# SmartSwitch2.net
KiCad netlist of a schematic drawn in EAGLE
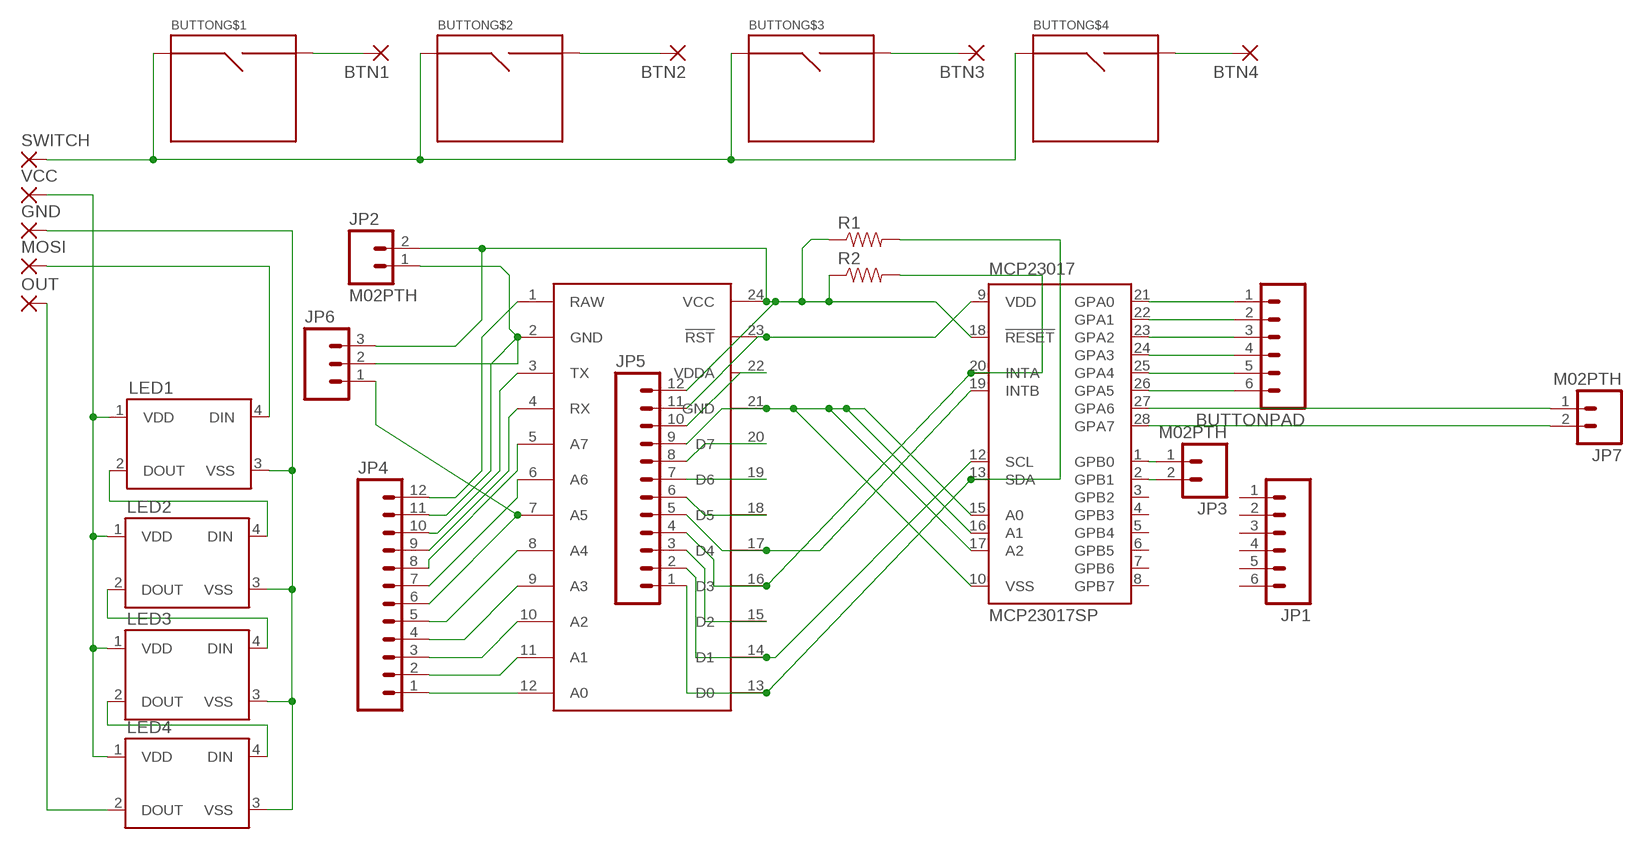
[diagram p0: schematic, sheet 1]

(export (version "E")
  (design (tool "Eeschema 10.0.6"))
  (components
    (comp (ref "BTN1")
      (value "2,15/1,0")
      (footprint "eagle-import:2,15_1,0")
      (libsource (lib "eagle-import") (part "2,15/1,0"))
    )
    (comp (ref "BTN2")
      (value "2,15/1,0")
      (footprint "eagle-import:2,15_1,0")
      (libsource (lib "eagle-import") (part "2,15/1,0"))
    )
    (comp (ref "BTN3")
      (value "2,15/1,0")
      (footprint "eagle-import:2,15_1,0")
      (libsource (lib "eagle-import") (part "2,15/1,0"))
    )
    (comp (ref "BTN4")
      (value "2,15/1,0")
      (footprint "eagle-import:2,15_1,0")
      (libsource (lib "eagle-import") (part "2,15/1,0"))
    )
    (comp (ref "BUTTON")
      (value "BUTTON")
      (footprint "eagle-import:BUTTON")
      (libsource (lib "eagle-import") (part "BUTTON"))
    )
    (comp (ref "BUTTONPAD")
      (value "M06SILK_FEMALE_PTH")
      (footprint "eagle-import:1X06")
      (libsource (lib "eagle-import") (part "M06SILK_FEMALE_PTH"))
    )
    (comp (ref "GND")
      (value "2,15/1,0")
      (footprint "eagle-import:2,15_1,0")
      (libsource (lib "eagle-import") (part "2,15/1,0"))
    )
    (comp (ref "JP1")
      (value "M06SILK_FEMALE_PTH")
      (footprint "eagle-import:1X06")
      (libsource (lib "eagle-import") (part "M06SILK_FEMALE_PTH"))
    )
    (comp (ref "JP2")
      (value "M02PTH")
      (footprint "eagle-import:1X02")
      (libsource (lib "eagle-import") (part "M02PTH"))
    )
    (comp (ref "JP3")
      (value "M02PTH")
      (footprint "eagle-import:1X02")
      (libsource (lib "eagle-import") (part "M02PTH"))
    )
    (comp (ref "JP4")
      (value "M12PTH")
      (footprint "eagle-import:1X12-SMALL-PADS")
      (libsource (lib "eagle-import") (part "M12PTH"))
    )
    (comp (ref "JP5")
      (value "M12PTH")
      (footprint "eagle-import:1X12-SMALL-PADS")
      (libsource (lib "eagle-import") (part "M12PTH"))
    )
    (comp (ref "JP6")
      (value "M03PTH")
      (footprint "eagle-import:1X03")
      (libsource (lib "eagle-import") (part "M03PTH"))
    )
    (comp (ref "JP7")
      (value "M02PTH")
      (footprint "eagle-import:1X02")
      (libsource (lib "eagle-import") (part "M02PTH"))
    )
    (comp (ref "LED1")
      (value "WS2812B")
      (footprint "eagle-import:WS2812B")
      (libsource (lib "eagle-import") (part "WS2812B"))
    )
    (comp (ref "LED2")
      (value "WS2812B")
      (footprint "eagle-import:WS2812B")
      (libsource (lib "eagle-import") (part "WS2812B"))
    )
    (comp (ref "LED3")
      (value "WS2812B")
      (footprint "eagle-import:WS2812B")
      (libsource (lib "eagle-import") (part "WS2812B"))
    )
    (comp (ref "LED4")
      (value "WS2812B")
      (footprint "eagle-import:WS2812B")
      (libsource (lib "eagle-import") (part "WS2812B"))
    )
    (comp (ref "MCP23017")
      (value "MCP23017SP")
      (footprint "eagle-import:DIL28-3")
      (libsource (lib "eagle-import") (part "MCP23017SP"))
    )
    (comp (ref "MOSI")
      (value "2,15/1,0")
      (footprint "eagle-import:2,15_1,0")
      (libsource (lib "eagle-import") (part "2,15/1,0"))
    )
    (comp (ref "OUT")
      (value "2,15/1,0")
      (footprint "eagle-import:2,15_1,0")
      (libsource (lib "eagle-import") (part "2,15/1,0"))
    )
    (comp (ref "R1")
      (value "RESISTORPTH-1/2W")
      (footprint "eagle-import:AXIAL-0.5")
      (libsource (lib "eagle-import") (part "RESISTORPTH-1/2W"))
    )
    (comp (ref "R2")
      (value "RESISTORPTH-1/2W")
      (footprint "eagle-import:AXIAL-0.5")
      (libsource (lib "eagle-import") (part "RESISTORPTH-1/2W"))
    )
    (comp (ref "SPARK")
      (value "SPARK_CORECORE")
      (footprint "eagle-import:SPARK_CORE")
      (libsource (lib "eagle-import") (part "SPARK_CORECORE"))
    )
    (comp (ref "SWITCH")
      (value "2,15/1,0")
      (footprint "eagle-import:2,15_1,0")
      (libsource (lib "eagle-import") (part "2,15/1,0"))
    )
    (comp (ref "VCC")
      (value "2,15/1,0")
      (footprint "eagle-import:2,15_1,0")
      (libsource (lib "eagle-import") (part "2,15/1,0"))
    )
  )
  (nets
    (net (code "1") (name "Net-(BTN1-P)") (class "Default")
      (node (ref "BTN1") (pin "1") (pinfunction "P_1") (pintype "passive"))
      (node (ref "BUTTON") (pin "SIG2") (pinfunction "SIG2_SIG2") (pintype "bidirectional"))
    )
    (net (code "2") (name "Net-(BTN2-P)") (class "Default")
      (node (ref "BTN2") (pin "1") (pinfunction "P_1") (pintype "passive"))
      (node (ref "BUTTON") (pin "SIG4") (pinfunction "SIG2_SIG4") (pintype "bidirectional"))
    )
    (net (code "3") (name "Net-(BTN3-P)") (class "Default")
      (node (ref "BTN3") (pin "1") (pinfunction "P_1") (pintype "passive"))
      (node (ref "BUTTON") (pin "SIG6") (pinfunction "SIG2_SIG6") (pintype "bidirectional"))
    )
    (net (code "4") (name "Net-(BTN4-P)") (class "Default")
      (node (ref "BTN4") (pin "1") (pinfunction "P_1") (pintype "passive"))
      (node (ref "BUTTON") (pin "SIG8") (pinfunction "SIG2_SIG8") (pintype "bidirectional"))
    )
    (net (code "5") (name "Net-(BUTTONB-SIG1)") (class "Default")
      (node (ref "BUTTON") (pin "SIG1") (pinfunction "SIG1_SIG1") (pintype "bidirectional"))
      (node (ref "BUTTON") (pin "SIG3") (pinfunction "SIG1_SIG3") (pintype "bidirectional"))
      (node (ref "BUTTON") (pin "SIG5") (pinfunction "SIG1_SIG5") (pintype "bidirectional"))
      (node (ref "BUTTON") (pin "SIG7") (pinfunction "SIG1_SIG7") (pintype "bidirectional"))
      (node (ref "SWITCH") (pin "1") (pinfunction "P_1") (pintype "passive"))
    )
    (net (code "6") (name "Net-(GND-P)") (class "Default")
      (node (ref "GND") (pin "1") (pinfunction "P_1") (pintype "passive"))
      (node (ref "LED1") (pin "3") (pinfunction "VSS_3") (pintype "power_in"))
      (node (ref "LED2") (pin "3") (pinfunction "VSS_3") (pintype "power_in"))
      (node (ref "LED3") (pin "3") (pinfunction "VSS_3") (pintype "power_in"))
      (node (ref "LED4") (pin "3") (pinfunction "VSS_3") (pintype "power_in"))
    )
    (net (code "7") (name "Net-(JP2-Pad1)") (class "Default")
      (node (ref "JP2") (pin "1") (pinfunction "1_1") (pintype "passive"))
      (node (ref "JP4") (pin "11") (pinfunction "11_11") (pintype "passive"))
      (node (ref "JP6") (pin "2") (pinfunction "2_2") (pintype "passive"))
      (node (ref "SPARK") (pin "2") (pinfunction "GND_2") (pintype "power_in"))
    )
    (net (code "8") (name "Net-(LED1-DIN)") (class "Default")
      (node (ref "LED1") (pin "4") (pinfunction "DIN_4") (pintype "input"))
      (node (ref "MOSI") (pin "1") (pinfunction "P_1") (pintype "passive"))
    )
    (net (code "9") (name "Net-(LED1-DOUT)") (class "Default")
      (node (ref "LED1") (pin "2") (pinfunction "DOUT_2") (pintype "output"))
      (node (ref "LED2") (pin "4") (pinfunction "DIN_4") (pintype "input"))
    )
    (net (code "10") (name "Net-(LED1-VDD)") (class "Default")
      (node (ref "LED1") (pin "1") (pinfunction "VDD_1") (pintype "power_in"))
      (node (ref "LED2") (pin "1") (pinfunction "VDD_1") (pintype "power_in"))
      (node (ref "LED3") (pin "1") (pinfunction "VDD_1") (pintype "power_in"))
      (node (ref "LED4") (pin "1") (pinfunction "VDD_1") (pintype "power_in"))
      (node (ref "VCC") (pin "1") (pinfunction "P_1") (pintype "passive"))
    )
    (net (code "11") (name "Net-(LED2-DOUT)") (class "Default")
      (node (ref "LED2") (pin "2") (pinfunction "DOUT_2") (pintype "output"))
      (node (ref "LED3") (pin "4") (pinfunction "DIN_4") (pintype "input"))
    )
    (net (code "12") (name "Net-(LED3-DOUT)") (class "Default")
      (node (ref "LED3") (pin "2") (pinfunction "DOUT_2") (pintype "output"))
      (node (ref "LED4") (pin "4") (pinfunction "DIN_4") (pintype "input"))
    )
    (net (code "13") (name "Net-(LED4-DOUT)") (class "Default")
      (node (ref "LED4") (pin "2") (pinfunction "DOUT_2") (pintype "output"))
      (node (ref "OUT") (pin "1") (pinfunction "P_1") (pintype "passive"))
    )
    (net (code "14") (name "Net-(MCP23017-A0)") (class "Default")
      (node (ref "JP5") (pin "9") (pinfunction "9_9") (pintype "passive"))
      (node (ref "MCP23017") (pin "10") (pinfunction "VSS_10") (pintype "power_in"))
      (node (ref "MCP23017") (pin "15") (pinfunction "A0_15") (pintype "input"))
      (node (ref "MCP23017") (pin "16") (pinfunction "A1_16") (pintype "input"))
      (node (ref "MCP23017") (pin "17") (pinfunction "A2_17") (pintype "input"))
      (node (ref "SPARK") (pin "21") (pinfunction "GND_21") (pintype "power_in"))
    )
    (net (code "15") (name "Net-(MCP23017-GPA0)") (class "Default")
      (node (ref "BUTTONPAD") (pin "1") (pinfunction "1_1") (pintype "passive"))
      (node (ref "MCP23017") (pin "21") (pinfunction "GPA0_21") (pintype "bidirectional"))
    )
    (net (code "16") (name "Net-(MCP23017-GPA1)") (class "Default")
      (node (ref "BUTTONPAD") (pin "2") (pinfunction "2_2") (pintype "passive"))
      (node (ref "MCP23017") (pin "22") (pinfunction "GPA1_22") (pintype "bidirectional"))
    )
    (net (code "17") (name "Net-(MCP23017-GPA2)") (class "Default")
      (node (ref "BUTTONPAD") (pin "3") (pinfunction "3_3") (pintype "passive"))
      (node (ref "MCP23017") (pin "23") (pinfunction "GPA2_23") (pintype "bidirectional"))
    )
    (net (code "18") (name "Net-(MCP23017-GPA3)") (class "Default")
      (node (ref "BUTTONPAD") (pin "4") (pinfunction "4_4") (pintype "passive"))
      (node (ref "MCP23017") (pin "24") (pinfunction "GPA3_24") (pintype "bidirectional"))
    )
    (net (code "19") (name "Net-(MCP23017-GPA4)") (class "Default")
      (node (ref "BUTTONPAD") (pin "5") (pinfunction "5_5") (pintype "passive"))
      (node (ref "MCP23017") (pin "25") (pinfunction "GPA4_25") (pintype "bidirectional"))
    )
    (net (code "20") (name "Net-(MCP23017-GPA5)") (class "Default")
      (node (ref "BUTTONPAD") (pin "6") (pinfunction "6_6") (pintype "passive"))
      (node (ref "MCP23017") (pin "26") (pinfunction "GPA5_26") (pintype "bidirectional"))
    )
    (net (code "21") (name "Net-(MCP23017-GPA6)") (class "Default")
      (node (ref "JP7") (pin "1") (pinfunction "1_1") (pintype "passive"))
      (node (ref "MCP23017") (pin "27") (pinfunction "GPA6_27") (pintype "bidirectional"))
    )
    (net (code "22") (name "Net-(MCP23017-GPA7)") (class "Default")
      (node (ref "JP7") (pin "2") (pinfunction "2_2") (pintype "passive"))
      (node (ref "MCP23017") (pin "28") (pinfunction "GPA7_28") (pintype "bidirectional"))
    )
    (net (code "23") (name "Net-(MCP23017-GPB0)") (class "Default")
      (node (ref "JP3") (pin "1") (pinfunction "1_1") (pintype "passive"))
      (node (ref "MCP23017") (pin "1") (pinfunction "GPB0_1") (pintype "bidirectional"))
    )
    (net (code "24") (name "Net-(MCP23017-GPB1)") (class "Default")
      (node (ref "JP3") (pin "2") (pinfunction "2_2") (pintype "passive"))
      (node (ref "MCP23017") (pin "2") (pinfunction "GPB1_2") (pintype "bidirectional"))
    )
    (net (code "25") (name "Net-(MCP23017-INTA)") (class "Default")
      (node (ref "JP5") (pin "4") (pinfunction "4_4") (pintype "passive"))
      (node (ref "MCP23017") (pin "20") (pinfunction "INTA_20") (pintype "output"))
      (node (ref "R2") (pin "P$2") (pinfunction "2_P$2") (pintype "passive"))
      (node (ref "SPARK") (pin "16") (pinfunction "D3_16") (pintype "bidirectional"))
    )
    (net (code "26") (name "Net-(MCP23017-INTB)") (class "Default")
      (node (ref "JP5") (pin "5") (pinfunction "5_5") (pintype "passive"))
      (node (ref "MCP23017") (pin "19") (pinfunction "INTB_19") (pintype "output"))
      (node (ref "SPARK") (pin "17") (pinfunction "D4_17") (pintype "bidirectional"))
    )
    (net (code "27") (name "Net-(MCP23017-SCL)") (class "Default")
      (node (ref "JP5") (pin "2") (pinfunction "2_2") (pintype "passive"))
      (node (ref "MCP23017") (pin "12") (pinfunction "SCL_12") (pintype "input"))
      (node (ref "SPARK") (pin "14") (pinfunction "D1_14") (pintype "bidirectional"))
    )
    (net (code "28") (name "Net-(MCP23017-SDA)") (class "Default")
      (node (ref "JP5") (pin "1") (pinfunction "1_1") (pintype "passive"))
      (node (ref "MCP23017") (pin "13") (pinfunction "SDA_13") (pintype "bidirectional"))
      (node (ref "R1") (pin "P$2") (pinfunction "2_P$2") (pintype "passive"))
      (node (ref "SPARK") (pin "13") (pinfunction "D0_13") (pintype "bidirectional"))
    )
    (net (code "29") (name "Net-(MCP23017-VDD)") (class "Default")
      (node (ref "JP5") (pin "11") (pinfunction "11_11") (pintype "passive"))
      (node (ref "MCP23017") (pin "9") (pinfunction "VDD_9") (pintype "power_in"))
      (node (ref "SPARK") (pin "23") (pinfunction "~{RST}_23") (pintype "bidirectional"))
    )
    (net (code "30") (name "Net-(MCP23017-~{RESET})") (class "Default")
      (node (ref "JP2") (pin "2") (pinfunction "2_2") (pintype "passive"))
      (node (ref "JP5") (pin "12") (pinfunction "12_12") (pintype "passive"))
      (node (ref "JP6") (pin "3") (pinfunction "3_3") (pintype "passive"))
      (node (ref "MCP23017") (pin "18") (pinfunction "~{RESET}_18") (pintype "input"))
      (node (ref "R1") (pin "P$1") (pinfunction "1_P$1") (pintype "passive"))
      (node (ref "R2") (pin "P$1") (pinfunction "1_P$1") (pintype "passive"))
      (node (ref "SPARK") (pin "24") (pinfunction "VCC_24") (pintype "power_in"))
    )
    (net (code "31") (name "Net-(SPARK-A0)") (class "Default")
      (node (ref "JP4") (pin "1") (pinfunction "1_1") (pintype "passive"))
      (node (ref "SPARK") (pin "12") (pinfunction "A0_12") (pintype "bidirectional"))
    )
    (net (code "32") (name "Net-(SPARK-A1)") (class "Default")
      (node (ref "JP4") (pin "2") (pinfunction "2_2") (pintype "passive"))
      (node (ref "SPARK") (pin "11") (pinfunction "A1_11") (pintype "bidirectional"))
    )
    (net (code "33") (name "Net-(SPARK-A2)") (class "Default")
      (node (ref "JP4") (pin "3") (pinfunction "3_3") (pintype "passive"))
      (node (ref "SPARK") (pin "10") (pinfunction "A2_10") (pintype "bidirectional"))
    )
    (net (code "34") (name "Net-(SPARK-A3)") (class "Default")
      (node (ref "JP4") (pin "4") (pinfunction "4_4") (pintype "passive"))
      (node (ref "SPARK") (pin "9") (pinfunction "A3_9") (pintype "bidirectional"))
    )
    (net (code "35") (name "Net-(SPARK-A4)") (class "Default")
      (node (ref "JP4") (pin "5") (pinfunction "5_5") (pintype "passive"))
      (node (ref "SPARK") (pin "8") (pinfunction "A4_8") (pintype "bidirectional"))
    )
    (net (code "36") (name "Net-(SPARK-A5)") (class "Default")
      (node (ref "JP4") (pin "6") (pinfunction "6_6") (pintype "passive"))
      (node (ref "JP6") (pin "1") (pinfunction "1_1") (pintype "passive"))
      (node (ref "SPARK") (pin "7") (pinfunction "A5_7") (pintype "bidirectional"))
    )
    (net (code "37") (name "Net-(SPARK-A6)") (class "Default")
      (node (ref "JP4") (pin "7") (pinfunction "7_7") (pintype "passive"))
      (node (ref "SPARK") (pin "6") (pinfunction "A6_6") (pintype "bidirectional"))
    )
    (net (code "38") (name "Net-(SPARK-A7)") (class "Default")
      (node (ref "JP4") (pin "8") (pinfunction "8_8") (pintype "passive"))
      (node (ref "SPARK") (pin "5") (pinfunction "A7_5") (pintype "bidirectional"))
    )
    (net (code "39") (name "Net-(SPARK-D2)") (class "Default")
      (node (ref "JP5") (pin "3") (pinfunction "3_3") (pintype "passive"))
      (node (ref "SPARK") (pin "15") (pinfunction "D2_15") (pintype "bidirectional"))
    )
    (net (code "40") (name "Net-(SPARK-D5)") (class "Default")
      (node (ref "JP5") (pin "6") (pinfunction "6_6") (pintype "passive"))
      (node (ref "SPARK") (pin "18") (pinfunction "D5_18") (pintype "bidirectional"))
    )
    (net (code "41") (name "Net-(SPARK-D6)") (class "Default")
      (node (ref "JP5") (pin "7") (pinfunction "7_7") (pintype "passive"))
      (node (ref "SPARK") (pin "19") (pinfunction "D6_19") (pintype "bidirectional"))
    )
    (net (code "42") (name "Net-(SPARK-D7)") (class "Default")
      (node (ref "JP5") (pin "8") (pinfunction "8_8") (pintype "passive"))
      (node (ref "SPARK") (pin "20") (pinfunction "D7_20") (pintype "bidirectional"))
    )
    (net (code "43") (name "Net-(SPARK-RAW)") (class "Default")
      (node (ref "JP4") (pin "12") (pinfunction "12_12") (pintype "passive"))
      (node (ref "SPARK") (pin "1") (pinfunction "RAW_1") (pintype "power_in"))
    )
    (net (code "44") (name "Net-(SPARK-RX)") (class "Default")
      (node (ref "JP4") (pin "9") (pinfunction "9_9") (pintype "passive"))
      (node (ref "SPARK") (pin "4") (pinfunction "RX_4") (pintype "bidirectional"))
    )
    (net (code "45") (name "Net-(SPARK-TX)") (class "Default")
      (node (ref "JP4") (pin "10") (pinfunction "10_10") (pintype "passive"))
      (node (ref "SPARK") (pin "3") (pinfunction "TX_3") (pintype "bidirectional"))
    )
    (net (code "46") (name "Net-(SPARK-VDDA)") (class "Default")
      (node (ref "JP5") (pin "10") (pinfunction "10_10") (pintype "passive"))
      (node (ref "SPARK") (pin "22") (pinfunction "VDDA_22") (pintype "power_in"))
    )
    (net (code "47") (name "unconnected-(JP1-Pad1)") (class "Default")
      (node (ref "JP1") (pin "1") (pinfunction "1_1") (pintype "passive"))
    )
    (net (code "48") (name "unconnected-(JP1-Pad2)") (class "Default")
      (node (ref "JP1") (pin "2") (pinfunction "2_2") (pintype "passive"))
    )
    (net (code "49") (name "unconnected-(JP1-Pad3)") (class "Default")
      (node (ref "JP1") (pin "3") (pinfunction "3_3") (pintype "passive"))
    )
    (net (code "50") (name "unconnected-(JP1-Pad4)") (class "Default")
      (node (ref "JP1") (pin "4") (pinfunction "4_4") (pintype "passive"))
    )
    (net (code "51") (name "unconnected-(JP1-Pad5)") (class "Default")
      (node (ref "JP1") (pin "5") (pinfunction "5_5") (pintype "passive"))
    )
    (net (code "52") (name "unconnected-(JP1-Pad6)") (class "Default")
      (node (ref "JP1") (pin "6") (pinfunction "6_6") (pintype "passive"))
    )
    (net (code "53") (name "unconnected-(MCP23017-GPB2-Pad3)") (class "Default")
      (node (ref "MCP23017") (pin "3") (pinfunction "GPB2_3") (pintype "bidirectional"))
    )
    (net (code "54") (name "unconnected-(MCP23017-GPB3-Pad4)") (class "Default")
      (node (ref "MCP23017") (pin "4") (pinfunction "GPB3_4") (pintype "bidirectional"))
    )
    (net (code "55") (name "unconnected-(MCP23017-GPB4-Pad5)") (class "Default")
      (node (ref "MCP23017") (pin "5") (pinfunction "GPB4_5") (pintype "bidirectional"))
    )
    (net (code "56") (name "unconnected-(MCP23017-GPB5-Pad6)") (class "Default")
      (node (ref "MCP23017") (pin "6") (pinfunction "GPB5_6") (pintype "bidirectional"))
    )
    (net (code "57") (name "unconnected-(MCP23017-GPB6-Pad7)") (class "Default")
      (node (ref "MCP23017") (pin "7") (pinfunction "GPB6_7") (pintype "bidirectional"))
    )
    (net (code "58") (name "unconnected-(MCP23017-GPB7-Pad8)") (class "Default")
      (node (ref "MCP23017") (pin "8") (pinfunction "GPB7_8") (pintype "bidirectional"))
    )
  )
)
